# laser_shield.net
KiCad netlist of a schematic drawn in EAGLE
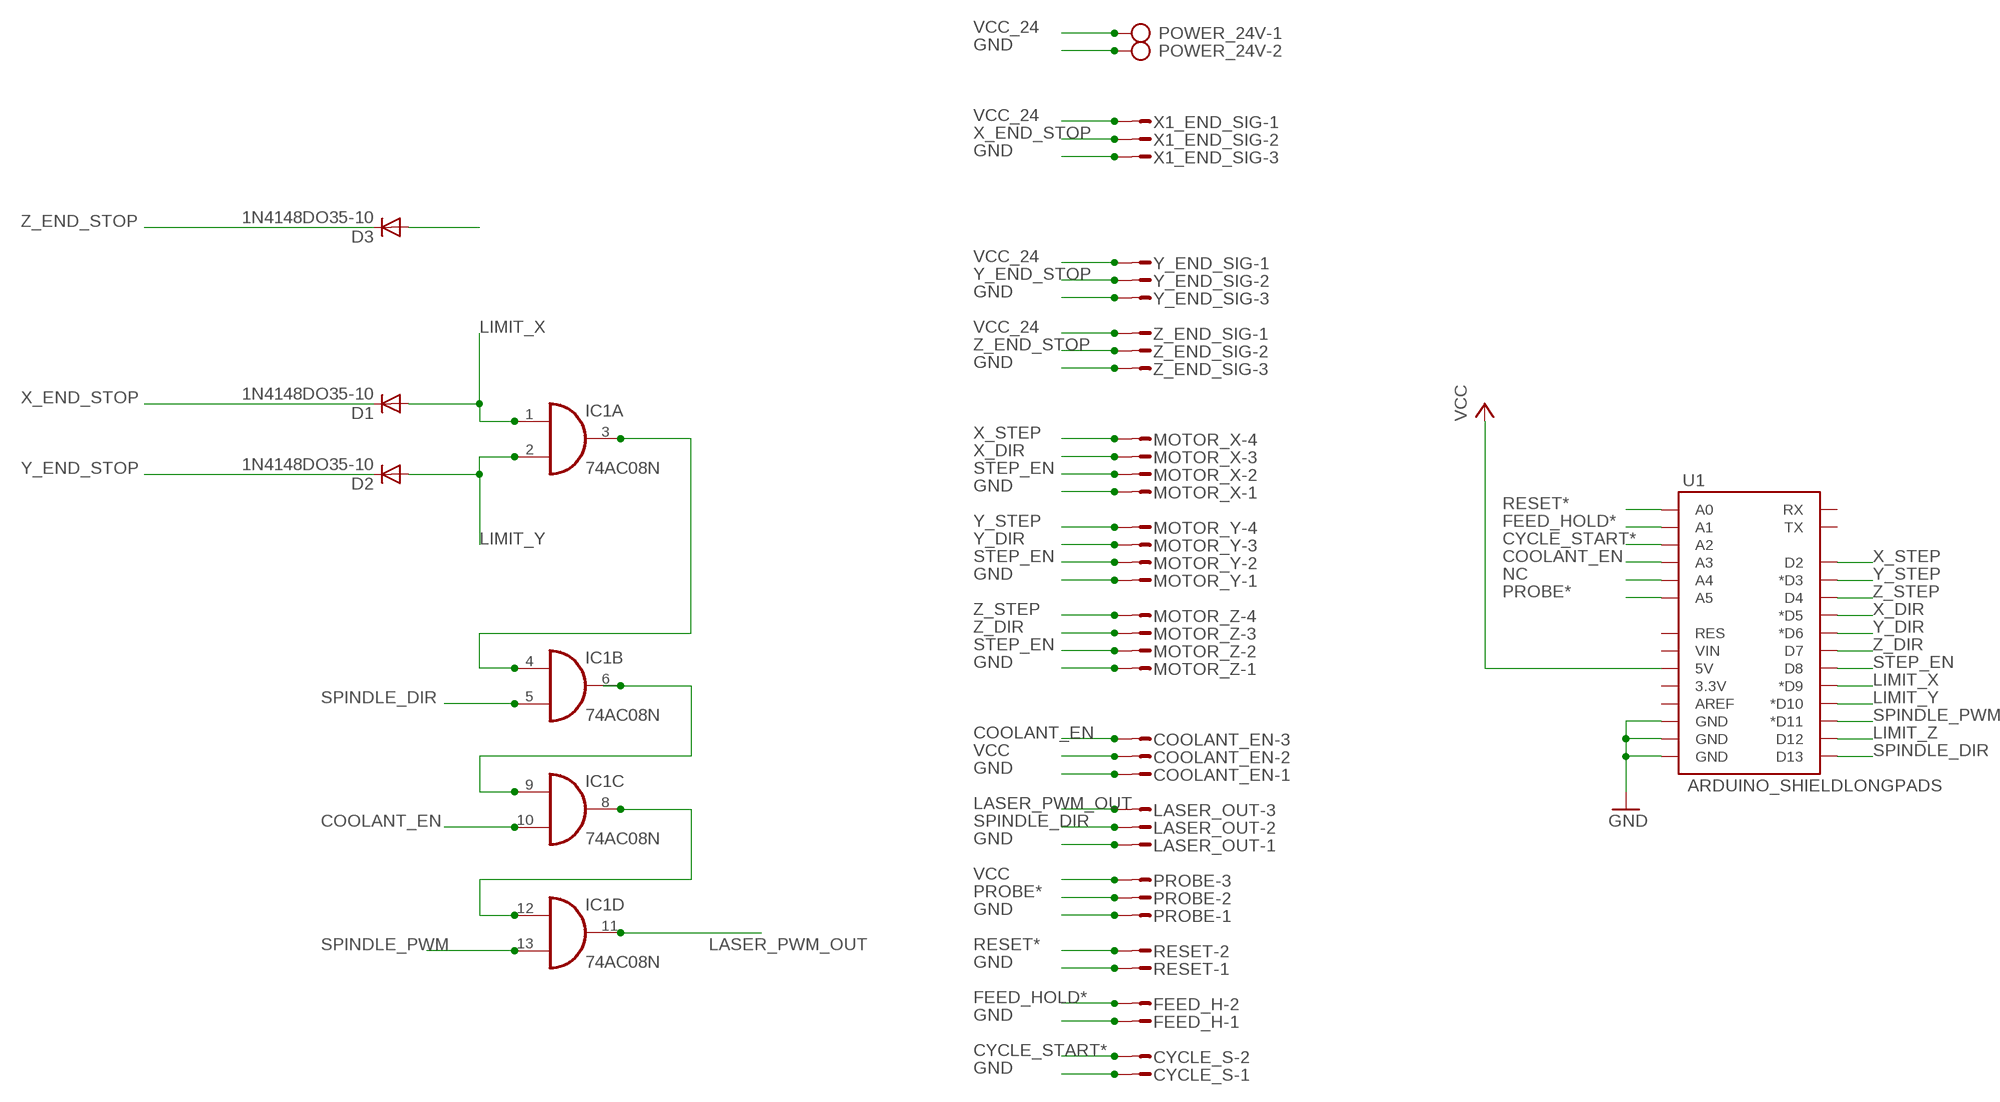
[diagram p0: schematic, sheet 1]

(export (version "E")
  (design (tool "Eeschema 10.0.6"))
  (components
    (comp (ref "COOLANT_EN")
      (value "L03P")
      (footprint "eagle-import:L03P")
      (libsource (lib "eagle-import") (part "L03P"))
    )
    (comp (ref "CYCLE_S")
      (value "L02P")
      (footprint "eagle-import:L02P")
      (libsource (lib "eagle-import") (part "L02P"))
    )
    (comp (ref "D1")
      (value "1N4148DO35-10")
      (footprint "eagle-import:DO35-10")
      (libsource (lib "eagle-import") (part "1N4148DO35-10"))
    )
    (comp (ref "D2")
      (value "1N4148DO35-10")
      (footprint "eagle-import:DO35-10")
      (libsource (lib "eagle-import") (part "1N4148DO35-10"))
    )
    (comp (ref "D3")
      (value "1N4148DO35-10")
      (footprint "eagle-import:DO35-10")
      (libsource (lib "eagle-import") (part "1N4148DO35-10"))
    )
    (comp (ref "FEED_H")
      (value "L02P")
      (footprint "eagle-import:L02P")
      (libsource (lib "eagle-import") (part "L02P"))
    )
    (comp (ref "IC1")
      (value "74AC08N")
      (footprint "eagle-import:DIL14")
      (libsource (lib "eagle-import") (part "7408NAC"))
    )
    (comp (ref "LASER_OUT")
      (value "L03P")
      (footprint "eagle-import:L03P")
      (libsource (lib "eagle-import") (part "L03P"))
    )
    (comp (ref "MOTOR_X")
      (value "L04P")
      (footprint "eagle-import:L04P")
      (libsource (lib "eagle-import") (part "L04P"))
    )
    (comp (ref "MOTOR_Y")
      (value "L04P")
      (footprint "eagle-import:L04P")
      (libsource (lib "eagle-import") (part "L04P"))
    )
    (comp (ref "MOTOR_Z")
      (value "L04P")
      (footprint "eagle-import:L04P")
      (libsource (lib "eagle-import") (part "L04P"))
    )
    (comp (ref "POWER_24V")
      (value "AK300/2")
      (footprint "eagle-import:AK300_2")
      (libsource (lib "eagle-import") (part "AK300/2"))
    )
    (comp (ref "PROBE")
      (value "L03P")
      (footprint "eagle-import:L03P")
      (libsource (lib "eagle-import") (part "L03P"))
    )
    (comp (ref "RESET")
      (value "L02P")
      (footprint "eagle-import:L02P")
      (libsource (lib "eagle-import") (part "L02P"))
    )
    (comp (ref "U1")
      (value "ARDUINO_SHIELDLONGPADS")
      (footprint "eagle-import:DUEMILANOVE_SHIELD_LONGPADS")
      (libsource (lib "eagle-import") (part "ARDUINO_SHIELDLONGPADS"))
    )
    (comp (ref "X1_END_SIG")
      (value "L03P")
      (footprint "eagle-import:L03P")
      (libsource (lib "eagle-import") (part "L03P"))
    )
    (comp (ref "Y_END_SIG")
      (value "L03P")
      (footprint "eagle-import:L03P")
      (libsource (lib "eagle-import") (part "L03P"))
    )
    (comp (ref "Z_END_SIG")
      (value "L03P")
      (footprint "eagle-import:L03P")
      (libsource (lib "eagle-import") (part "L03P"))
    )
  )
  (nets
    (net (code "1") (name "/COOLANT_EN") (class "Default")
      (node (ref "COOLANT_EN") (pin "3") (pinfunction "S_3") (pintype "passive"))
      (node (ref "IC1") (pin "10") (pinfunction "I1_10") (pintype "input"))
      (node (ref "U1") (pin "A3") (pinfunction "A3_A3") (pintype "bidirectional"))
    )
    (net (code "2") (name "/CYCLE_START*") (class "Default")
      (node (ref "CYCLE_S") (pin "2") (pinfunction "S_2") (pintype "passive"))
      (node (ref "U1") (pin "A2") (pinfunction "A2_A2") (pintype "bidirectional"))
    )
    (net (code "3") (name "/FEED_HOLD*") (class "Default")
      (node (ref "FEED_H") (pin "2") (pinfunction "S_2") (pintype "passive"))
      (node (ref "U1") (pin "A1") (pinfunction "A1_A1") (pintype "bidirectional"))
    )
    (net (code "4") (name "/LASER_PWM_OUT") (class "Default")
      (node (ref "IC1") (pin "11") (pinfunction "O_11") (pintype "output"))
      (node (ref "LASER_OUT") (pin "3") (pinfunction "S_3") (pintype "passive"))
    )
    (net (code "5") (name "/LIMIT_X") (class "Default")
      (node (ref "D1") (pin "A") (pinfunction "A_A") (pintype "passive"))
      (node (ref "IC1") (pin "1") (pinfunction "I0_1") (pintype "input"))
      (node (ref "U1") (pin "D9") (pinfunction "*D9_D9") (pintype "bidirectional"))
    )
    (net (code "6") (name "/LIMIT_Y") (class "Default")
      (node (ref "D2") (pin "A") (pinfunction "A_A") (pintype "passive"))
      (node (ref "IC1") (pin "2") (pinfunction "I1_2") (pintype "input"))
      (node (ref "U1") (pin "D10") (pinfunction "*D10_D10") (pintype "bidirectional"))
    )
    (net (code "7") (name "/LIMIT_Z") (class "Default")
      (node (ref "D3") (pin "A") (pinfunction "A_A") (pintype "passive"))
      (node (ref "U1") (pin "D12") (pinfunction "D12_D12") (pintype "bidirectional"))
    )
    (net (code "8") (name "/NC") (class "Default")
      (node (ref "U1") (pin "A4") (pinfunction "A4_A4") (pintype "bidirectional"))
    )
    (net (code "9") (name "/PROBE*") (class "Default")
      (node (ref "PROBE") (pin "2") (pinfunction "S_2") (pintype "passive"))
      (node (ref "U1") (pin "A5") (pinfunction "A5_A5") (pintype "bidirectional"))
    )
    (net (code "10") (name "/RESET*") (class "Default")
      (node (ref "RESET") (pin "2") (pinfunction "S_2") (pintype "passive"))
      (node (ref "U1") (pin "A0") (pinfunction "A0_A0") (pintype "bidirectional"))
    )
    (net (code "11") (name "/SPINDLE_DIR") (class "Default")
      (node (ref "IC1") (pin "5") (pinfunction "I1_5") (pintype "input"))
      (node (ref "LASER_OUT") (pin "2") (pinfunction "S_2") (pintype "passive"))
      (node (ref "U1") (pin "D13") (pinfunction "D13_D13") (pintype "bidirectional"))
    )
    (net (code "12") (name "/SPINDLE_PWM") (class "Default")
      (node (ref "IC1") (pin "13") (pinfunction "I1_13") (pintype "input"))
      (node (ref "U1") (pin "D11") (pinfunction "*D11_D11") (pintype "bidirectional"))
    )
    (net (code "13") (name "/STEP_EN") (class "Default")
      (node (ref "MOTOR_X") (pin "2") (pinfunction "S_2") (pintype "passive"))
      (node (ref "MOTOR_Y") (pin "2") (pinfunction "S_2") (pintype "passive"))
      (node (ref "MOTOR_Z") (pin "2") (pinfunction "S_2") (pintype "passive"))
      (node (ref "U1") (pin "D8") (pinfunction "D8_D8") (pintype "bidirectional"))
    )
    (net (code "14") (name "/VCC_24") (class "Default")
      (node (ref "POWER_24V") (pin "1") (pinfunction "KL_1") (pintype "passive"))
      (node (ref "X1_END_SIG") (pin "1") (pinfunction "S_1") (pintype "passive"))
      (node (ref "Y_END_SIG") (pin "1") (pinfunction "S_1") (pintype "passive"))
      (node (ref "Z_END_SIG") (pin "1") (pinfunction "S_1") (pintype "passive"))
    )
    (net (code "15") (name "/X_DIR") (class "Default")
      (node (ref "MOTOR_X") (pin "3") (pinfunction "S_3") (pintype "passive"))
      (node (ref "U1") (pin "D5") (pinfunction "*D5_D5") (pintype "bidirectional"))
    )
    (net (code "16") (name "/X_END_STOP") (class "Default")
      (node (ref "D1") (pin "C") (pinfunction "C_C") (pintype "passive"))
      (node (ref "X1_END_SIG") (pin "2") (pinfunction "S_2") (pintype "passive"))
    )
    (net (code "17") (name "/X_STEP") (class "Default")
      (node (ref "MOTOR_X") (pin "4") (pinfunction "S_4") (pintype "passive"))
      (node (ref "U1") (pin "D2") (pinfunction "D2_D2") (pintype "bidirectional"))
    )
    (net (code "18") (name "/Y_DIR") (class "Default")
      (node (ref "MOTOR_Y") (pin "3") (pinfunction "S_3") (pintype "passive"))
      (node (ref "U1") (pin "D6") (pinfunction "*D6_D6") (pintype "bidirectional"))
    )
    (net (code "19") (name "/Y_END_STOP") (class "Default")
      (node (ref "D2") (pin "C") (pinfunction "C_C") (pintype "passive"))
      (node (ref "Y_END_SIG") (pin "2") (pinfunction "S_2") (pintype "passive"))
    )
    (net (code "20") (name "/Y_STEP") (class "Default")
      (node (ref "MOTOR_Y") (pin "4") (pinfunction "S_4") (pintype "passive"))
      (node (ref "U1") (pin "D3") (pinfunction "*D3_D3") (pintype "bidirectional"))
    )
    (net (code "21") (name "/Z_DIR") (class "Default")
      (node (ref "MOTOR_Z") (pin "3") (pinfunction "S_3") (pintype "passive"))
      (node (ref "U1") (pin "D7") (pinfunction "D7_D7") (pintype "bidirectional"))
    )
    (net (code "22") (name "/Z_END_STOP") (class "Default")
      (node (ref "D3") (pin "C") (pinfunction "C_C") (pintype "passive"))
      (node (ref "Z_END_SIG") (pin "2") (pinfunction "S_2") (pintype "passive"))
    )
    (net (code "23") (name "/Z_STEP") (class "Default")
      (node (ref "MOTOR_Z") (pin "4") (pinfunction "S_4") (pintype "passive"))
      (node (ref "U1") (pin "D4") (pinfunction "D4_D4") (pintype "bidirectional"))
    )
    (net (code "24") (name "GND") (class "Default")
      (node (ref "COOLANT_EN") (pin "1") (pinfunction "S_1") (pintype "passive"))
      (node (ref "CYCLE_S") (pin "1") (pinfunction "S_1") (pintype "passive"))
      (node (ref "FEED_H") (pin "1") (pinfunction "S_1") (pintype "passive"))
      (node (ref "LASER_OUT") (pin "1") (pinfunction "S_1") (pintype "passive"))
      (node (ref "MOTOR_X") (pin "1") (pinfunction "S_1") (pintype "passive"))
      (node (ref "MOTOR_Y") (pin "1") (pinfunction "S_1") (pintype "passive"))
      (node (ref "MOTOR_Z") (pin "1") (pinfunction "S_1") (pintype "passive"))
      (node (ref "POWER_24V") (pin "2") (pinfunction "KL_2") (pintype "passive"))
      (node (ref "PROBE") (pin "1") (pinfunction "S_1") (pintype "passive"))
      (node (ref "RESET") (pin "1") (pinfunction "S_1") (pintype "passive"))
      (node (ref "U1") (pin "GND@0") (pinfunction "GND_GND@0") (pintype "bidirectional"))
      (node (ref "U1") (pin "GND@1") (pinfunction "GND_GND@1") (pintype "bidirectional"))
      (node (ref "U1") (pin "GND@2") (pinfunction "GND_GND@2") (pintype "bidirectional"))
      (node (ref "X1_END_SIG") (pin "3") (pinfunction "S_3") (pintype "passive"))
      (node (ref "Y_END_SIG") (pin "3") (pinfunction "S_3") (pintype "passive"))
      (node (ref "Z_END_SIG") (pin "3") (pinfunction "S_3") (pintype "passive"))
    )
    (net (code "25") (name "Net-(IC1A-O)") (class "Default")
      (node (ref "IC1") (pin "3") (pinfunction "O_3") (pintype "output"))
      (node (ref "IC1") (pin "4") (pinfunction "I0_4") (pintype "input"))
    )
    (net (code "26") (name "Net-(IC1B-O)") (class "Default")
      (node (ref "IC1") (pin "6") (pinfunction "O_6") (pintype "output"))
      (node (ref "IC1") (pin "9") (pinfunction "I0_9") (pintype "input"))
    )
    (net (code "27") (name "Net-(IC1C-O)") (class "Default")
      (node (ref "IC1") (pin "12") (pinfunction "I0_12") (pintype "input"))
      (node (ref "IC1") (pin "8") (pinfunction "O_8") (pintype "output"))
    )
    (net (code "28") (name "VCC") (class "Default")
      (node (ref "COOLANT_EN") (pin "2") (pinfunction "S_2") (pintype "passive"))
      (node (ref "PROBE") (pin "3") (pinfunction "S_3") (pintype "passive"))
      (node (ref "U1") (pin "5V") (pinfunction "5V_5V") (pintype "bidirectional"))
    )
    (net (code "29") (name "unconnected-(U1-Pad3.3V)") (class "Default")
      (node (ref "U1") (pin "3.3V") (pinfunction "3.3V_3.3V") (pintype "bidirectional"))
    )
    (net (code "30") (name "unconnected-(U1-PadAREF)") (class "Default")
      (node (ref "U1") (pin "AREF") (pinfunction "AREF_AREF") (pintype "bidirectional"))
    )
    (net (code "31") (name "unconnected-(U1-PadRES)") (class "Default")
      (node (ref "U1") (pin "RES") (pinfunction "RES_RES") (pintype "bidirectional"))
    )
    (net (code "32") (name "unconnected-(U1-PadRX)") (class "Default")
      (node (ref "U1") (pin "RX") (pinfunction "RX_RX") (pintype "bidirectional"))
    )
    (net (code "33") (name "unconnected-(U1-PadTX)") (class "Default")
      (node (ref "U1") (pin "TX") (pinfunction "TX_TX") (pintype "bidirectional"))
    )
    (net (code "34") (name "unconnected-(U1-PadVIN)") (class "Default")
      (node (ref "U1") (pin "VIN") (pinfunction "VIN_VIN") (pintype "bidirectional"))
    )
  )
)
